# ORD_POWER.net
KiCad netlist of a schematic drawn in Altium Designer
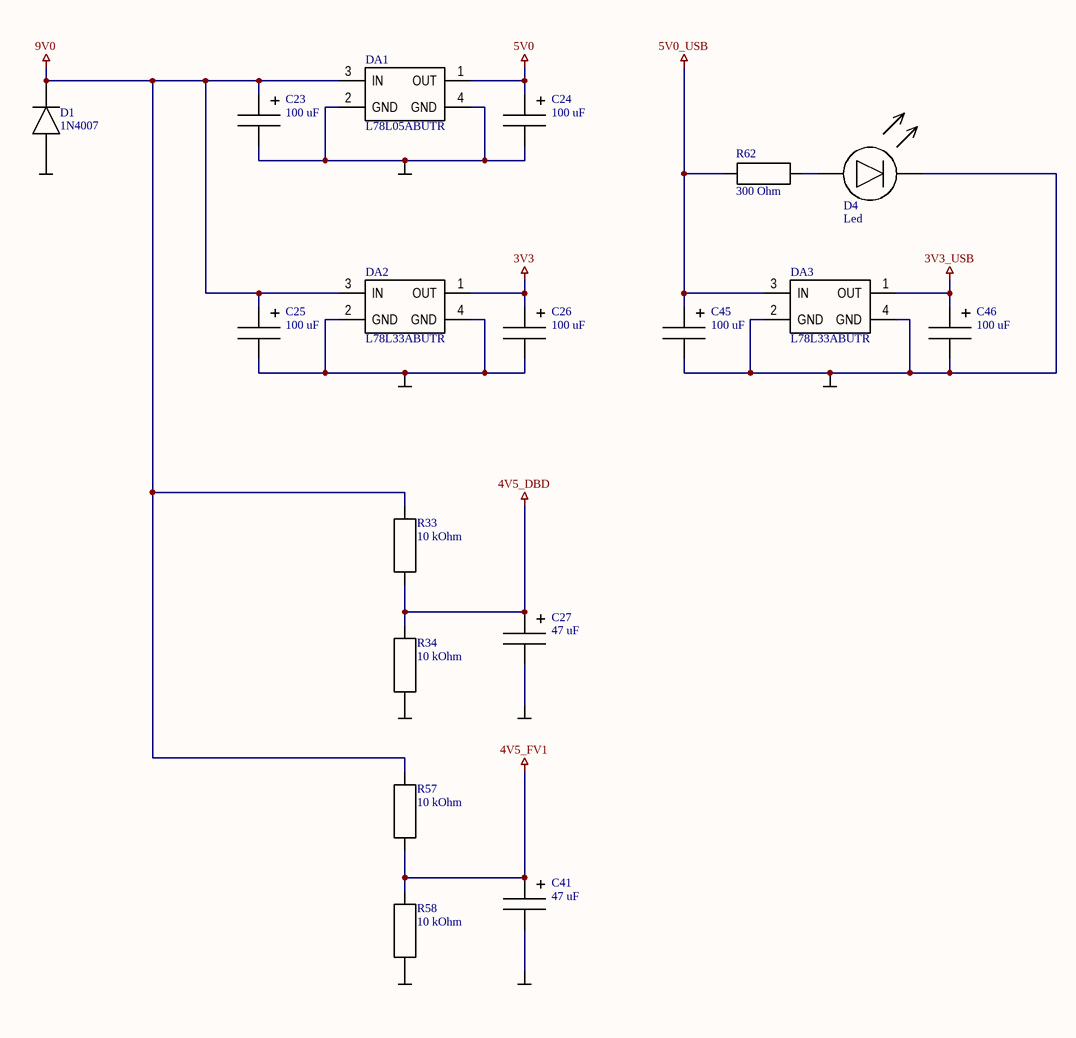
[diagram p0: ORD_POWER.SchDoc]

(export (version "E")
  (design (tool "Eeschema 10.0.6"))
  (components
    (comp (ref "C23")
      (value "100 uF")
      (footprint "K50-35")
      (libsource (lib "Gost_passive_lib") (part "Capacitor_Pol"))
    )
    (comp (ref "C24")
      (value "100 uF")
      (footprint "K50-35")
      (libsource (lib "Gost_passive_lib") (part "Capacitor_Pol"))
    )
    (comp (ref "C25")
      (value "100 uF")
      (footprint "K50-35")
      (libsource (lib "Gost_passive_lib") (part "Capacitor_Pol"))
    )
    (comp (ref "C26")
      (value "100 uF")
      (footprint "K50-35")
      (libsource (lib "Gost_passive_lib") (part "Capacitor_Pol"))
    )
    (comp (ref "C27")
      (value "47 uF")
      (footprint "C3528_CASE-B")
      (libsource (lib "Gost_passive_lib") (part "Capacitor_Pol"))
    )
    (comp (ref "C41")
      (value "47 uF")
      (footprint "C3528_CASE-B")
      (libsource (lib "Gost_passive_lib") (part "Capacitor_Pol"))
    )
    (comp (ref "C45")
      (value "100 uF")
      (footprint "K50-35")
      (libsource (lib "Gost_passive_lib") (part "Capacitor_Pol"))
    )
    (comp (ref "C46")
      (value "100 uF")
      (footprint "K50-35")
      (libsource (lib "Gost_passive_lib") (part "Capacitor_Pol"))
    )
    (comp (ref "D1")
      (value "1N4007")
      (footprint "DO-41")
      (libsource (lib "Gost_passive_lib") (part "1N4007"))
    )
    (comp (ref "D4") (value "Led") (footprint "LED") (libsource (lib "Gost_passive_lib") (part "Led")))
    (comp (ref "DA1")
      (value "L78L05ABUTR")
      (footprint "SOT-89")
      (fields
        (field (name "MANUFACTURER_PART_NUMBER") "NJM78L05UA-TE1")
        (field (name "RS PART NUMBER") "7139502P")
      )
      (libsource (lib "Gost_power_libs") (part "L78L05ABUTR"))
    )
    (comp (ref "DA2")
      (value "L78L33ABUTR")
      (footprint "SOT-89")
      (fields
        (field (name "MANUFACTURER_PART_NUMBER") "NJM78L05UA-TE1")
        (field (name "RS PART NUMBER") "7139502P")
      )
      (libsource (lib "Gost_power_libs") (part "L78L33ABUTR"))
    )
    (comp (ref "DA3")
      (value "L78L33ABUTR")
      (footprint "SOT-89")
      (fields
        (field (name "MANUFACTURER_PART_NUMBER") "NJM78L05UA-TE1")
        (field (name "RS PART NUMBER") "7139502P")
      )
      (libsource (lib "Gost_power_libs") (part "L78L33ABUTR"))
    )
    (comp (ref "R33")
      (value "10 kOhm")
      (footprint "R0805[2012]")
      (libsource (lib "Gost_passive_lib") (part "Resistor"))
    )
    (comp (ref "R34")
      (value "10 kOhm")
      (footprint "R0805[2012]")
      (libsource (lib "Gost_passive_lib") (part "Resistor"))
    )
    (comp (ref "R57")
      (value "10 kOhm")
      (footprint "R0805[2012]")
      (libsource (lib "Gost_passive_lib") (part "Resistor"))
    )
    (comp (ref "R58")
      (value "10 kOhm")
      (footprint "R0805[2012]")
      (libsource (lib "Gost_passive_lib") (part "Resistor"))
    )
    (comp (ref "R62")
      (value "300 Ohm")
      (footprint "R0805[2012]")
      (libsource (lib "Gost_passive_lib") (part "Resistor"))
    )
  )
  (nets
    (net (code "1") (name "3V3") (class "Default")
      (node (ref "C26") (pin "1") (pinfunction "1_1") (pintype "passive"))
      (node (ref "DA2") (pin "1") (pinfunction "OUT_1") (pintype "passive"))
    )
    (net (code "2") (name "3V3_USB") (class "Default")
      (node (ref "C46") (pin "1") (pinfunction "1_1") (pintype "passive"))
      (node (ref "DA3") (pin "1") (pinfunction "OUT_1") (pintype "passive"))
    )
    (net (code "3") (name "4V5_DBD") (class "Default")
      (node (ref "C27") (pin "1") (pinfunction "1_1") (pintype "passive"))
      (node (ref "R33") (pin "1") (pinfunction "1_1") (pintype "passive"))
      (node (ref "R34") (pin "2") (pinfunction "2_2") (pintype "passive"))
    )
    (net (code "4") (name "4V5_FV1") (class "Default")
      (node (ref "C41") (pin "1") (pinfunction "1_1") (pintype "passive"))
      (node (ref "R57") (pin "1") (pinfunction "1_1") (pintype "passive"))
      (node (ref "R58") (pin "2") (pinfunction "2_2") (pintype "passive"))
    )
    (net (code "5") (name "5V0") (class "Default")
      (node (ref "C24") (pin "1") (pinfunction "1_1") (pintype "passive"))
      (node (ref "DA1") (pin "1") (pinfunction "OUT_1") (pintype "passive"))
    )
    (net (code "6") (name "5V0_USB") (class "Default")
      (node (ref "C45") (pin "1") (pinfunction "1_1") (pintype "passive"))
      (node (ref "DA3") (pin "3") (pinfunction "IN_3") (pintype "passive"))
      (node (ref "R62") (pin "2") (pinfunction "2_2") (pintype "passive"))
    )
    (net (code "7") (name "9V0") (class "Default")
      (node (ref "C23") (pin "1") (pinfunction "1_1") (pintype "passive"))
      (node (ref "C25") (pin "1") (pinfunction "1_1") (pintype "passive"))
      (node (ref "D1") (pin "1") (pinfunction "K_1") (pintype "passive"))
      (node (ref "DA1") (pin "3") (pinfunction "IN_3") (pintype "passive"))
      (node (ref "DA2") (pin "3") (pinfunction "IN_3") (pintype "passive"))
      (node (ref "R33") (pin "2") (pinfunction "2_2") (pintype "passive"))
      (node (ref "R57") (pin "2") (pinfunction "2_2") (pintype "passive"))
    )
    (net (code "8") (name "GND") (class "Default")
      (node (ref "C23") (pin "2") (pinfunction "2_2") (pintype "passive"))
      (node (ref "C24") (pin "2") (pinfunction "2_2") (pintype "passive"))
      (node (ref "C25") (pin "2") (pinfunction "2_2") (pintype "passive"))
      (node (ref "C26") (pin "2") (pinfunction "2_2") (pintype "passive"))
      (node (ref "C27") (pin "2") (pinfunction "2_2") (pintype "passive"))
      (node (ref "C41") (pin "2") (pinfunction "2_2") (pintype "passive"))
      (node (ref "C45") (pin "2") (pinfunction "2_2") (pintype "passive"))
      (node (ref "C46") (pin "2") (pinfunction "2_2") (pintype "passive"))
      (node (ref "D1") (pin "2") (pinfunction "A_2") (pintype "passive"))
      (node (ref "D4") (pin "2") (pinfunction "2_2") (pintype "passive"))
      (node (ref "DA1") (pin "2") (pinfunction "GND_2") (pintype "passive"))
      (node (ref "DA1") (pin "4") (pinfunction "GND_4") (pintype "passive"))
      (node (ref "DA2") (pin "2") (pinfunction "GND_2") (pintype "passive"))
      (node (ref "DA2") (pin "4") (pinfunction "GND_4") (pintype "passive"))
      (node (ref "DA3") (pin "2") (pinfunction "GND_2") (pintype "passive"))
      (node (ref "DA3") (pin "4") (pinfunction "GND_4") (pintype "passive"))
      (node (ref "R34") (pin "1") (pinfunction "1_1") (pintype "passive"))
      (node (ref "R58") (pin "1") (pinfunction "1_1") (pintype "passive"))
    )
    (net (code "9") (name "Net-(D4-Pad1)") (class "Default")
      (node (ref "D4") (pin "1") (pinfunction "1_1") (pintype "passive"))
      (node (ref "R62") (pin "1") (pinfunction "1_1") (pintype "passive"))
    )
  )
)
